# sync_rectification_module.net
KiCad netlist of a schematic drawn in Altium Designer
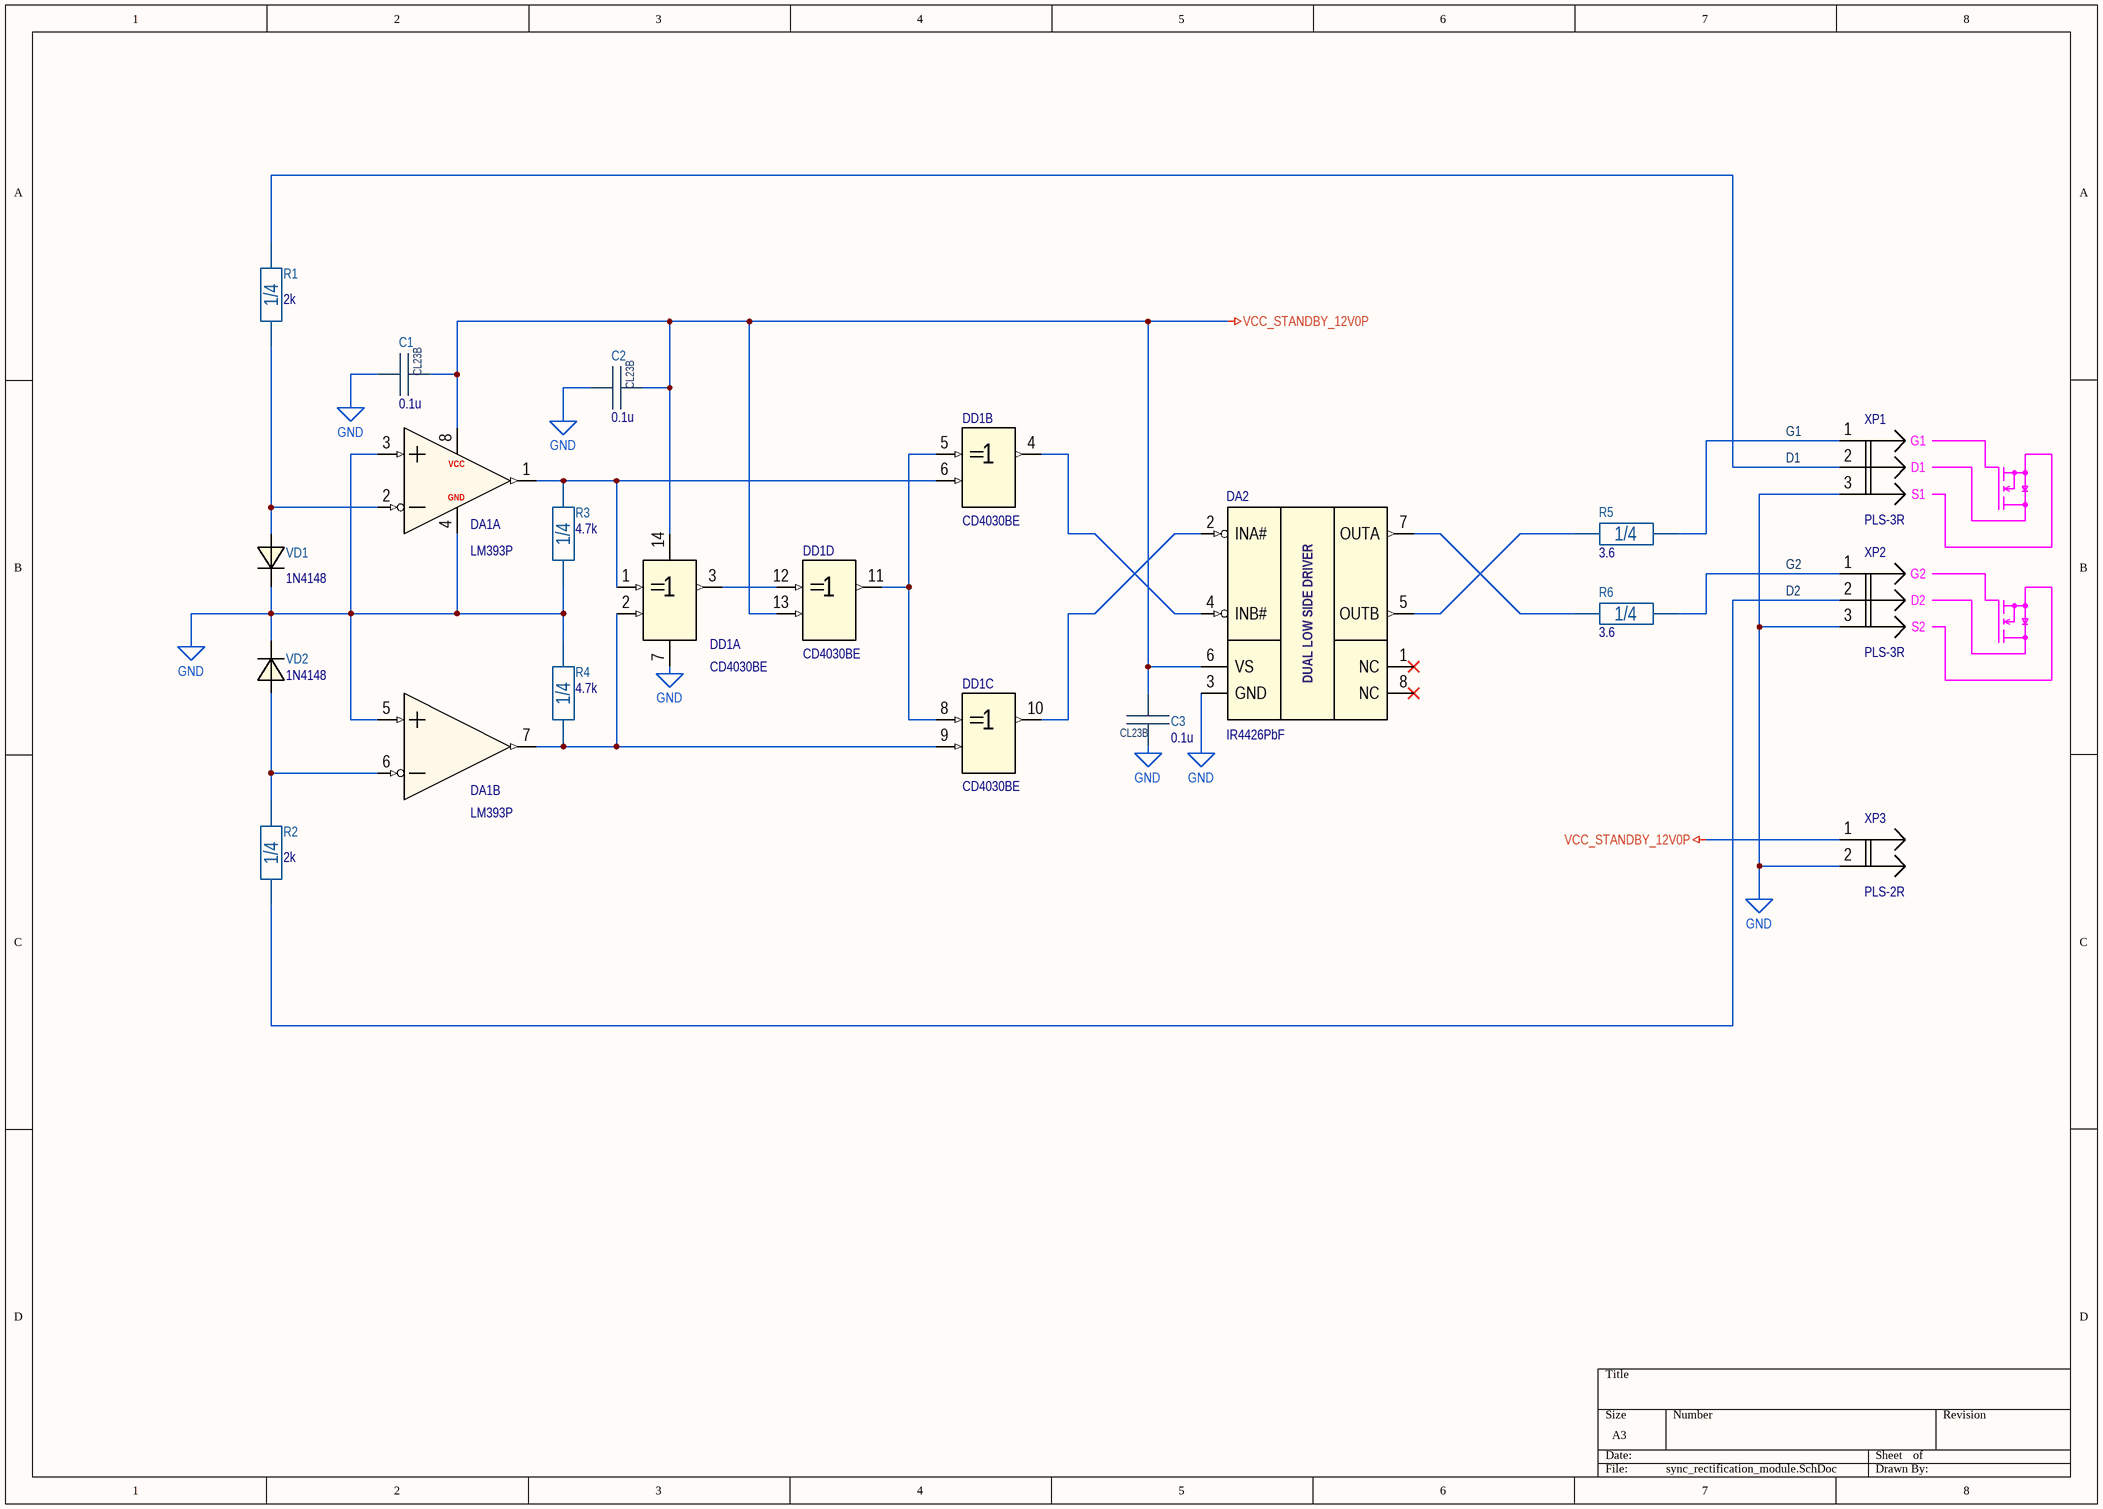
[diagram p0: sync_rectification_module.SchDoc]

(export (version "E")
  (design (tool "Eeschema 10.0.6"))
  (components
    (comp (ref "C1")
      (value "0.1u")
      (footprint "PcbLib_RC:CL23B_7.2x2.5")
      (description "Box-type metallized polyester film capacitor")
      (fields
        (field (name "TOLERANCE") "± * %")
        (field (name "VOLTAGE") "63V")
        (field (name "PACKAGE") "CL23B")
      )
      (libsource (lib "Schlib_RC") (part "CL23B"))
    )
    (comp (ref "C2")
      (value "0.1u")
      (footprint "PcbLib_RC:CL23B_7.2x2.5")
      (description "Box-type metallized polyester film capacitor")
      (fields
        (field (name "TOLERANCE") "± * %")
        (field (name "VOLTAGE") "63V")
        (field (name "PACKAGE") "CL23B")
      )
      (libsource (lib "Schlib_RC") (part "CL23B"))
    )
    (comp (ref "C3")
      (value "0.1u")
      (footprint "PcbLib_RC:CL23B_7.2x2.5")
      (description "Box-type metallized polyester film capacitor")
      (fields
        (field (name "TOLERANCE") "± * %")
        (field (name "VOLTAGE") "63V")
        (field (name "PACKAGE") "CL23B")
      )
      (libsource (lib "Schlib_RC") (part "CL23B"))
    )
    (comp (ref "DA1")
      (value "LM393P")
      (footprint "PcbLib_ICs:DIP-8P-M01_with_SO8")
      (description "Dual Comparator")
      (fields (field (name "MANUFACTURER") "Texas Instruments"))
      (libsource (lib "Schlib_Texas_Instruments") (part "LM393P"))
    )
    (comp (ref "DA2")
      (value "IR4426PbF")
      (footprint "PcbLib_ICs:DIP-8P-M01_with_SO8")
      (description "DUAL LOW SIDE DRIVER")
      (fields (field (name "MANUFACTURER") "International Rectifier"))
      (libsource (lib "Schlib_Infineon") (part "IR4426PbF"))
    )
    (comp (ref "DD1")
      (value "CD4030BE")
      (footprint "PcbLib_ICs:DIP-14P-M02")
      (description "Quad XOR-Gate")
      (fields (field (name "MANUFACTURER") "Texas Instruments"))
      (libsource (lib "Schlib_Texas_Instruments") (part "CD4030BE"))
    )
    (comp (ref "R1")
      (value "2k")
      (footprint "PcbLib_RC:CFR-25(VERTICAL)")
      (description "Resistor 1/4W")
      (fields
        (field (name "TOLERANCE") "± 1 %")
        (field (name "PART NUMBER") "MFR-25FTF52-2K")
        (field (name "PACKAGE") "1/4")
      )
      (libsource (lib "Schlib_RC") (part "CF25"))
    )
    (comp (ref "R2")
      (value "2k")
      (footprint "PcbLib_RC:CFR-25")
      (description "Resistor 1/4W")
      (fields
        (field (name "TOLERANCE") "± 1 %")
        (field (name "PART NUMBER") "MFR-25FTF52-2K")
        (field (name "PACKAGE") "1/4")
      )
      (libsource (lib "Schlib_RC") (part "CF25"))
    )
    (comp (ref "R3")
      (value "4.7k")
      (footprint "PcbLib_RC:CFR-25(VERTICAL)")
      (description "Resistor 1/4W")
      (fields
        (field (name "TOLERANCE") "± 1 %")
        (field (name "PART NUMBER") "MFR-25FTF52-4K7")
        (field (name "PACKAGE") "1/4")
      )
      (libsource (lib "Schlib_RC") (part "CF25"))
    )
    (comp (ref "R4")
      (value "4.7k")
      (footprint "PcbLib_RC:CFR-25(VERTICAL)")
      (description "Resistor 1/4W")
      (fields
        (field (name "TOLERANCE") "± 1 %")
        (field (name "PART NUMBER") "MFR-25FTF52-4K7")
        (field (name "PACKAGE") "1/4")
      )
      (libsource (lib "Schlib_RC") (part "CF25"))
    )
    (comp (ref "R5")
      (value "3.6")
      (footprint "PcbLib_RC:CFR-25(VERTICAL)")
      (description "Resistor 1/4W")
      (fields
        (field (name "TOLERANCE") "± 1 %")
        (field (name "PART NUMBER") "MFR-25FTF52-3R6")
        (field (name "PACKAGE") "1/4")
      )
      (libsource (lib "Schlib_RC") (part "CF25"))
    )
    (comp (ref "R6")
      (value "3.6")
      (footprint "PcbLib_RC:CFR-25")
      (description "Resistor 1/4W")
      (fields
        (field (name "TOLERANCE") "± 1 %")
        (field (name "PART NUMBER") "MFR-25FTF52-3R6")
        (field (name "PACKAGE") "1/4")
      )
      (libsource (lib "Schlib_RC") (part "CF25"))
    )
    (comp (ref "VD1")
      (value "1N4148")
      (footprint "PcbLib_Discrete:DO-35 GLASS LIGHT RED")
      (description "High-speed diode")
      (libsource (lib "Schlib_NXP_Semiconductors") (part "1N4148"))
    )
    (comp (ref "VD2")
      (value "1N4148")
      (footprint "PcbLib_Discrete:DO-35 GLASS LIGHT RED")
      (description "High-speed diode")
      (libsource (lib "Schlib_NXP_Semiconductors") (part "1N4148"))
    )
    (comp (ref "XP1")
      (value "PLS-3R")
      (footprint "PcbLib_Pin_Headers:PLS-3R")
      (libsource (lib "Schlib_Pin_Headers") (part "PLS-3R"))
    )
    (comp (ref "XP2")
      (value "PLS-3R")
      (footprint "PcbLib_Pin_Headers:PLS-3R")
      (libsource (lib "Schlib_Pin_Headers") (part "PLS-3R"))
    )
    (comp (ref "XP3")
      (value "PLS-2R")
      (footprint "PcbLib_Pin_Headers:PLS-2R")
      (libsource (lib "Schlib_Pin_Headers") (part "PLS-2R"))
    )
  )
  (nets
    (net (code "1") (name "/D1") (class "Default")
      (node (ref "R1") (pin "2") (pinfunction "2_2") (pintype "passive"))
      (node (ref "XP1") (pin "2") (pinfunction "2_2") (pintype "passive"))
    )
    (net (code "2") (name "/D2") (class "Default")
      (node (ref "R2") (pin "1") (pinfunction "1_1") (pintype "passive"))
      (node (ref "XP2") (pin "2") (pinfunction "2_2") (pintype "passive"))
    )
    (net (code "3") (name "/G1") (class "Default")
      (node (ref "R5") (pin "2") (pinfunction "2_2") (pintype "passive"))
      (node (ref "XP1") (pin "1") (pinfunction "1_1") (pintype "passive"))
    )
    (net (code "4") (name "/G2") (class "Default")
      (node (ref "R6") (pin "2") (pinfunction "2_2") (pintype "passive"))
      (node (ref "XP2") (pin "1") (pinfunction "1_1") (pintype "passive"))
    )
    (net (code "5") (name "GND") (class "Default")
      (node (ref "C1") (pin "2") (pinfunction "2_2") (pintype "passive"))
      (node (ref "C2") (pin "2") (pinfunction "2_2") (pintype "passive"))
      (node (ref "C3") (pin "2") (pinfunction "2_2") (pintype "passive"))
      (node (ref "DA1") (pin "3") (pinfunction "1IN+_3") (pintype "input"))
      (node (ref "DA1") (pin "4") (pinfunction "GND_4") (pintype "power_in"))
      (node (ref "DA1") (pin "5") (pinfunction "2IN+_5") (pintype "input"))
      (node (ref "DA2") (pin "3") (pinfunction "GND_3") (pintype "power_in"))
      (node (ref "DD1") (pin "7") (pinfunction "GND_7") (pintype "power_in"))
      (node (ref "R3") (pin "2") (pinfunction "2_2") (pintype "passive"))
      (node (ref "R4") (pin "2") (pinfunction "2_2") (pintype "passive"))
      (node (ref "VD1") (pin "1") (pinfunction "1_1") (pintype "passive"))
      (node (ref "VD2") (pin "1") (pinfunction "1_1") (pintype "passive"))
      (node (ref "XP1") (pin "3") (pinfunction "3_3") (pintype "passive"))
      (node (ref "XP2") (pin "3") (pinfunction "3_3") (pintype "passive"))
      (node (ref "XP3") (pin "2") (pinfunction "2_2") (pintype "passive"))
    )
    (net (code "6") (name "Net-(DA1A-1IN-)") (class "Default")
      (node (ref "DA1") (pin "2") (pinfunction "1IN-_2") (pintype "input"))
      (node (ref "R1") (pin "1") (pinfunction "1_1") (pintype "passive"))
      (node (ref "VD1") (pin "2") (pinfunction "2_2") (pintype "passive"))
    )
    (net (code "7") (name "Net-(DA1A-1OUT)") (class "Default")
      (node (ref "DA1") (pin "1") (pinfunction "1OUT_1") (pintype "output"))
      (node (ref "DD1") (pin "1") (pinfunction "A0_1") (pintype "input"))
      (node (ref "DD1") (pin "6") (pinfunction "B1_6") (pintype "input"))
      (node (ref "R3") (pin "1") (pinfunction "1_1") (pintype "passive"))
    )
    (net (code "8") (name "Net-(DA1B-2IN-)") (class "Default")
      (node (ref "DA1") (pin "6") (pinfunction "2IN-_6") (pintype "input"))
      (node (ref "R2") (pin "2") (pinfunction "2_2") (pintype "passive"))
      (node (ref "VD2") (pin "2") (pinfunction "2_2") (pintype "passive"))
    )
    (net (code "9") (name "Net-(DA1B-2OUT)") (class "Default")
      (node (ref "DA1") (pin "7") (pinfunction "2OUT_7") (pintype "output"))
      (node (ref "DD1") (pin "2") (pinfunction "B0_2") (pintype "input"))
      (node (ref "DD1") (pin "9") (pinfunction "B2_9") (pintype "input"))
      (node (ref "R4") (pin "1") (pinfunction "1_1") (pintype "passive"))
    )
    (net (code "10") (name "Net-(DA2-INA#)") (class "Default")
      (node (ref "DA2") (pin "2") (pinfunction "INA#_2") (pintype "input"))
      (node (ref "DD1") (pin "10") (pinfunction "Y2_10") (pintype "output"))
    )
    (net (code "11") (name "Net-(DA2-INB#)") (class "Default")
      (node (ref "DA2") (pin "4") (pinfunction "INB#_4") (pintype "input"))
      (node (ref "DD1") (pin "4") (pinfunction "Y1_4") (pintype "output"))
    )
    (net (code "12") (name "Net-(DA2-OUTA)") (class "Default")
      (node (ref "DA2") (pin "7") (pinfunction "OUTA_7") (pintype "output"))
      (node (ref "R6") (pin "1") (pinfunction "1_1") (pintype "passive"))
    )
    (net (code "13") (name "Net-(DA2-OUTB)") (class "Default")
      (node (ref "DA2") (pin "5") (pinfunction "OUTB_5") (pintype "output"))
      (node (ref "R5") (pin "1") (pinfunction "1_1") (pintype "passive"))
    )
    (net (code "14") (name "Net-(DD1A-Y0)") (class "Default")
      (node (ref "DD1") (pin "12") (pinfunction "A3_12") (pintype "input"))
      (node (ref "DD1") (pin "3") (pinfunction "Y0_3") (pintype "output"))
    )
    (net (code "15") (name "Net-(DD1B-A1)") (class "Default")
      (node (ref "DD1") (pin "11") (pinfunction "Y3_11") (pintype "output"))
      (node (ref "DD1") (pin "5") (pinfunction "A1_5") (pintype "input"))
      (node (ref "DD1") (pin "8") (pinfunction "A2_8") (pintype "input"))
    )
    (net (code "16") (name "VCC_STANDBY_12V0P") (class "Default")
      (node (ref "C1") (pin "1") (pinfunction "1_1") (pintype "passive"))
      (node (ref "C2") (pin "1") (pinfunction "1_1") (pintype "passive"))
      (node (ref "C3") (pin "1") (pinfunction "1_1") (pintype "passive"))
      (node (ref "DA1") (pin "8") (pinfunction "VCC_8") (pintype "power_in"))
      (node (ref "DA2") (pin "6") (pinfunction "VS_6") (pintype "power_in"))
      (node (ref "DD1") (pin "13") (pinfunction "B3_13") (pintype "input"))
      (node (ref "DD1") (pin "14") (pinfunction "VCC_14") (pintype "power_in"))
      (node (ref "XP3") (pin "1") (pinfunction "1_1") (pintype "passive"))
    )
    (net (code "17") (name "unconnected-(DA2-NC-Pad1)") (class "Default")
      (node (ref "DA2") (pin "1") (pinfunction "NC_1") (pintype "tri_state+no_connect"))
    )
    (net (code "18") (name "unconnected-(DA2-NC-Pad8)") (class "Default")
      (node (ref "DA2") (pin "8") (pinfunction "NC_8") (pintype "tri_state+no_connect"))
    )
  )
)
